# kbd.net
KiCad netlist of a schematic drawn in Altium Designer
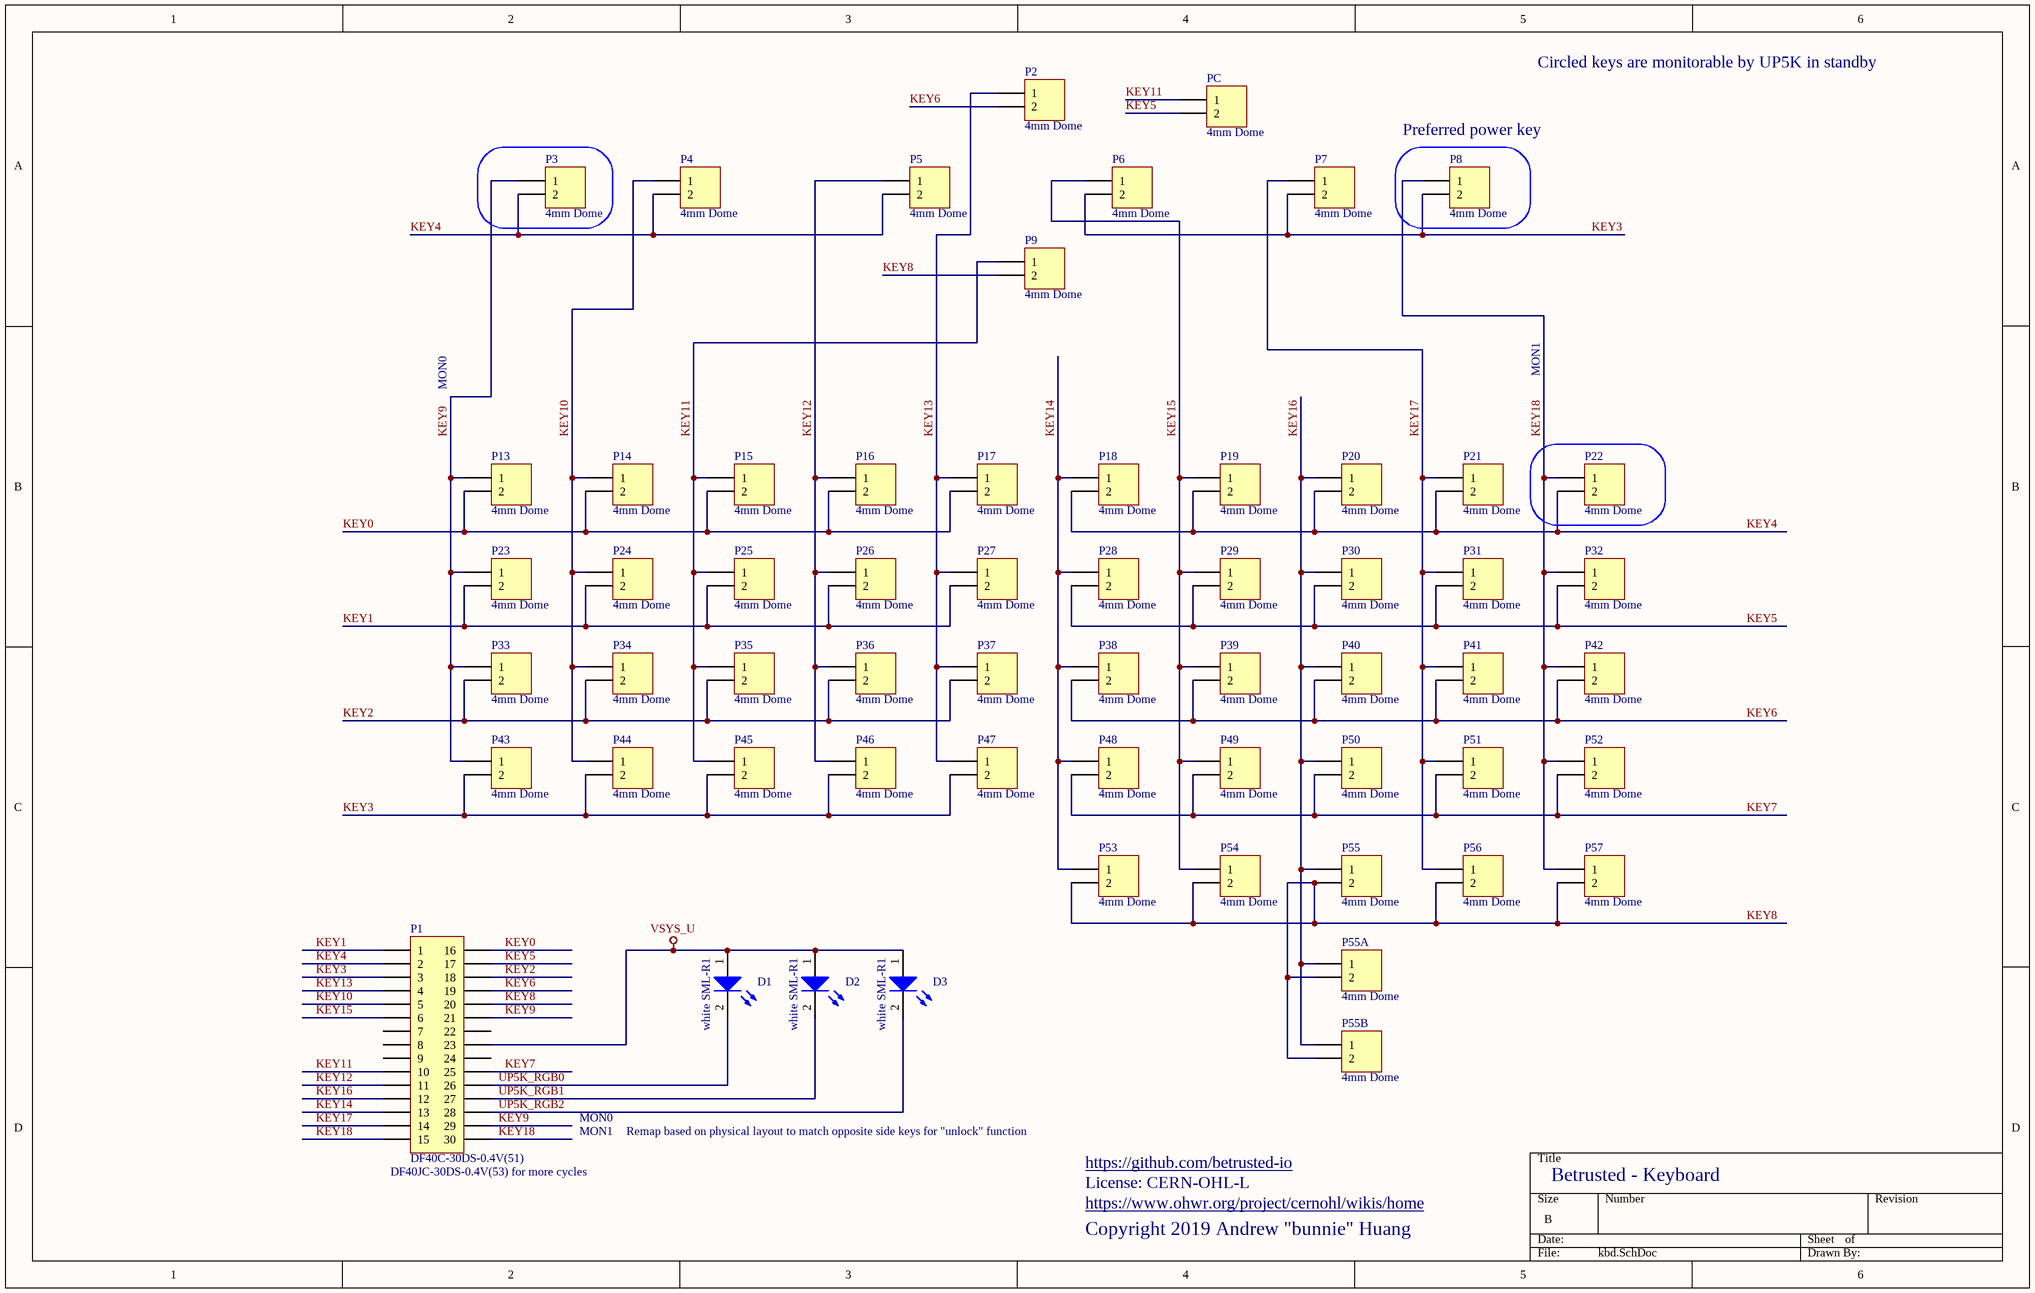
[diagram p0: kbd.SchDoc]

(export (version "E")
  (design (tool "Eeschema 10.0.6"))
  (components
    (comp (ref "D1")
      (value "white SML-R1")
      (footprint "ROHM_SML-R1")
      (description "Red LED")
      (fields (field (name "MPN") "SMLR13WBDW") (field (name "PUBLISHER") "Altium Limited"))
      (libsource (lib "Miscellaneous Devices") (part "LED2"))
    )
    (comp (ref "D2")
      (value "white SML-R1")
      (footprint "ROHM_SML-R1")
      (description "Red LED")
      (fields (field (name "MPN") "SMLR13WBDW") (field (name "PUBLISHER") "Altium Limited"))
      (libsource (lib "Miscellaneous Devices") (part "LED2"))
    )
    (comp (ref "D3")
      (value "white SML-R1")
      (footprint "ROHM_SML-R1")
      (description "Red LED")
      (fields (field (name "MPN") "SMLR13WBDW") (field (name "PUBLISHER") "Altium Limited"))
      (libsource (lib "Miscellaneous Devices") (part "LED2"))
    )
    (comp (ref "P1")
      (value "DF40C-30DS-0.4V(51)")
      (footprint "HRS_DF40C-30DS-0.4V(51)")
      (description "Header, 15-Pin, Dual row")
      (fields (field (name "PUBLISHER") "Altium Limited"))
      (libsource (lib "Miscellaneous Connectors") (part "Header 15X2A"))
    )
    (comp (ref "P2")
      (value "4mm Dome")
      (footprint "4MM_DOME_SW")
      (description "Header, 2-Pin")
      (fields (field (name "PUBLISHER") "Altium Limited"))
      (libsource (lib "Miscellaneous Connectors") (part "Header 2"))
    )
    (comp (ref "P3")
      (value "4mm Dome")
      (footprint "4MM_DOME_SW")
      (description "Header, 2-Pin")
      (fields (field (name "PUBLISHER") "Altium Limited"))
      (libsource (lib "Miscellaneous Connectors") (part "Header 2"))
    )
    (comp (ref "P4")
      (value "4mm Dome")
      (footprint "4MM_DOME_SW")
      (description "Header, 2-Pin")
      (fields (field (name "PUBLISHER") "Altium Limited"))
      (libsource (lib "Miscellaneous Connectors") (part "Header 2"))
    )
    (comp (ref "P5")
      (value "4mm Dome")
      (footprint "4MM_DOME_SW")
      (description "Header, 2-Pin")
      (fields (field (name "PUBLISHER") "Altium Limited"))
      (libsource (lib "Miscellaneous Connectors") (part "Header 2"))
    )
    (comp (ref "P6")
      (value "4mm Dome")
      (footprint "4MM_DOME_SW")
      (description "Header, 2-Pin")
      (fields (field (name "PUBLISHER") "Altium Limited"))
      (libsource (lib "Miscellaneous Connectors") (part "Header 2"))
    )
    (comp (ref "P7")
      (value "4mm Dome")
      (footprint "4MM_DOME_SW")
      (description "Header, 2-Pin")
      (fields (field (name "PUBLISHER") "Altium Limited"))
      (libsource (lib "Miscellaneous Connectors") (part "Header 2"))
    )
    (comp (ref "P8")
      (value "4mm Dome")
      (footprint "4MM_DOME_SW")
      (description "Header, 2-Pin")
      (fields (field (name "PUBLISHER") "Altium Limited"))
      (libsource (lib "Miscellaneous Connectors") (part "Header 2"))
    )
    (comp (ref "P9")
      (value "4mm Dome")
      (footprint "4MM_DOME_SW")
      (description "Header, 2-Pin")
      (fields (field (name "PUBLISHER") "Altium Limited"))
      (libsource (lib "Miscellaneous Connectors") (part "Header 2"))
    )
    (comp (ref "P13")
      (value "4mm Dome")
      (footprint "4MM_DOME_SW")
      (description "Header, 2-Pin")
      (fields (field (name "PUBLISHER") "Altium Limited"))
      (libsource (lib "Miscellaneous Connectors") (part "Header 2"))
    )
    (comp (ref "P14")
      (value "4mm Dome")
      (footprint "4MM_DOME_SW")
      (description "Header, 2-Pin")
      (fields (field (name "PUBLISHER") "Altium Limited"))
      (libsource (lib "Miscellaneous Connectors") (part "Header 2"))
    )
    (comp (ref "P15")
      (value "4mm Dome")
      (footprint "4MM_DOME_SW")
      (description "Header, 2-Pin")
      (fields (field (name "PUBLISHER") "Altium Limited"))
      (libsource (lib "Miscellaneous Connectors") (part "Header 2"))
    )
    (comp (ref "P16")
      (value "4mm Dome")
      (footprint "4MM_DOME_SW")
      (description "Header, 2-Pin")
      (fields (field (name "PUBLISHER") "Altium Limited"))
      (libsource (lib "Miscellaneous Connectors") (part "Header 2"))
    )
    (comp (ref "P17")
      (value "4mm Dome")
      (footprint "4MM_DOME_SW")
      (description "Header, 2-Pin")
      (fields (field (name "PUBLISHER") "Altium Limited"))
      (libsource (lib "Miscellaneous Connectors") (part "Header 2"))
    )
    (comp (ref "P18")
      (value "4mm Dome")
      (footprint "4MM_DOME_SW")
      (description "Header, 2-Pin")
      (fields (field (name "PUBLISHER") "Altium Limited"))
      (libsource (lib "Miscellaneous Connectors") (part "Header 2"))
    )
    (comp (ref "P19")
      (value "4mm Dome")
      (footprint "4MM_DOME_SW")
      (description "Header, 2-Pin")
      (fields (field (name "PUBLISHER") "Altium Limited"))
      (libsource (lib "Miscellaneous Connectors") (part "Header 2"))
    )
    (comp (ref "P20")
      (value "4mm Dome")
      (footprint "4MM_DOME_SW")
      (description "Header, 2-Pin")
      (fields (field (name "PUBLISHER") "Altium Limited"))
      (libsource (lib "Miscellaneous Connectors") (part "Header 2"))
    )
    (comp (ref "P21")
      (value "4mm Dome")
      (footprint "4MM_DOME_SW")
      (description "Header, 2-Pin")
      (fields (field (name "PUBLISHER") "Altium Limited"))
      (libsource (lib "Miscellaneous Connectors") (part "Header 2"))
    )
    (comp (ref "P22")
      (value "4mm Dome")
      (footprint "4MM_DOME_SW")
      (description "Header, 2-Pin")
      (fields (field (name "PUBLISHER") "Altium Limited"))
      (libsource (lib "Miscellaneous Connectors") (part "Header 2"))
    )
    (comp (ref "P23")
      (value "4mm Dome")
      (footprint "4MM_DOME_SW")
      (description "Header, 2-Pin")
      (fields (field (name "PUBLISHER") "Altium Limited"))
      (libsource (lib "Miscellaneous Connectors") (part "Header 2"))
    )
    (comp (ref "P24")
      (value "4mm Dome")
      (footprint "4MM_DOME_SW")
      (description "Header, 2-Pin")
      (fields (field (name "PUBLISHER") "Altium Limited"))
      (libsource (lib "Miscellaneous Connectors") (part "Header 2"))
    )
    (comp (ref "P25")
      (value "4mm Dome")
      (footprint "4MM_DOME_SW")
      (description "Header, 2-Pin")
      (fields (field (name "PUBLISHER") "Altium Limited"))
      (libsource (lib "Miscellaneous Connectors") (part "Header 2"))
    )
    (comp (ref "P26")
      (value "4mm Dome")
      (footprint "4MM_DOME_SW")
      (description "Header, 2-Pin")
      (fields (field (name "PUBLISHER") "Altium Limited"))
      (libsource (lib "Miscellaneous Connectors") (part "Header 2"))
    )
    (comp (ref "P27")
      (value "4mm Dome")
      (footprint "4MM_DOME_SW")
      (description "Header, 2-Pin")
      (fields (field (name "PUBLISHER") "Altium Limited"))
      (libsource (lib "Miscellaneous Connectors") (part "Header 2"))
    )
    (comp (ref "P28")
      (value "4mm Dome")
      (footprint "4MM_DOME_SW")
      (description "Header, 2-Pin")
      (fields (field (name "PUBLISHER") "Altium Limited"))
      (libsource (lib "Miscellaneous Connectors") (part "Header 2"))
    )
    (comp (ref "P29")
      (value "4mm Dome")
      (footprint "4MM_DOME_SW")
      (description "Header, 2-Pin")
      (fields (field (name "PUBLISHER") "Altium Limited"))
      (libsource (lib "Miscellaneous Connectors") (part "Header 2"))
    )
    (comp (ref "P30")
      (value "4mm Dome")
      (footprint "4MM_DOME_SW")
      (description "Header, 2-Pin")
      (fields (field (name "PUBLISHER") "Altium Limited"))
      (libsource (lib "Miscellaneous Connectors") (part "Header 2"))
    )
    (comp (ref "P31")
      (value "4mm Dome")
      (footprint "4MM_DOME_SW")
      (description "Header, 2-Pin")
      (fields (field (name "PUBLISHER") "Altium Limited"))
      (libsource (lib "Miscellaneous Connectors") (part "Header 2"))
    )
    (comp (ref "P32")
      (value "4mm Dome")
      (footprint "4MM_DOME_SW")
      (description "Header, 2-Pin")
      (fields (field (name "PUBLISHER") "Altium Limited"))
      (libsource (lib "Miscellaneous Connectors") (part "Header 2"))
    )
    (comp (ref "P33")
      (value "4mm Dome")
      (footprint "4MM_DOME_SW")
      (description "Header, 2-Pin")
      (fields (field (name "PUBLISHER") "Altium Limited"))
      (libsource (lib "Miscellaneous Connectors") (part "Header 2"))
    )
    (comp (ref "P34")
      (value "4mm Dome")
      (footprint "4MM_DOME_SW")
      (description "Header, 2-Pin")
      (fields (field (name "PUBLISHER") "Altium Limited"))
      (libsource (lib "Miscellaneous Connectors") (part "Header 2"))
    )
    (comp (ref "P35")
      (value "4mm Dome")
      (footprint "4MM_DOME_SW")
      (description "Header, 2-Pin")
      (fields (field (name "PUBLISHER") "Altium Limited"))
      (libsource (lib "Miscellaneous Connectors") (part "Header 2"))
    )
    (comp (ref "P36")
      (value "4mm Dome")
      (footprint "4MM_DOME_SW")
      (description "Header, 2-Pin")
      (fields (field (name "PUBLISHER") "Altium Limited"))
      (libsource (lib "Miscellaneous Connectors") (part "Header 2"))
    )
    (comp (ref "P37")
      (value "4mm Dome")
      (footprint "4MM_DOME_SW")
      (description "Header, 2-Pin")
      (fields (field (name "PUBLISHER") "Altium Limited"))
      (libsource (lib "Miscellaneous Connectors") (part "Header 2"))
    )
    (comp (ref "P38")
      (value "4mm Dome")
      (footprint "4MM_DOME_SW")
      (description "Header, 2-Pin")
      (fields (field (name "PUBLISHER") "Altium Limited"))
      (libsource (lib "Miscellaneous Connectors") (part "Header 2"))
    )
    (comp (ref "P39")
      (value "4mm Dome")
      (footprint "4MM_DOME_SW")
      (description "Header, 2-Pin")
      (fields (field (name "PUBLISHER") "Altium Limited"))
      (libsource (lib "Miscellaneous Connectors") (part "Header 2"))
    )
    (comp (ref "P40")
      (value "4mm Dome")
      (footprint "4MM_DOME_SW")
      (description "Header, 2-Pin")
      (fields (field (name "PUBLISHER") "Altium Limited"))
      (libsource (lib "Miscellaneous Connectors") (part "Header 2"))
    )
    (comp (ref "P41")
      (value "4mm Dome")
      (footprint "4MM_DOME_SW")
      (description "Header, 2-Pin")
      (fields (field (name "PUBLISHER") "Altium Limited"))
      (libsource (lib "Miscellaneous Connectors") (part "Header 2"))
    )
    (comp (ref "P42")
      (value "4mm Dome")
      (footprint "4MM_DOME_SW")
      (description "Header, 2-Pin")
      (fields (field (name "PUBLISHER") "Altium Limited"))
      (libsource (lib "Miscellaneous Connectors") (part "Header 2"))
    )
    (comp (ref "P43")
      (value "4mm Dome")
      (footprint "4MM_DOME_SW")
      (description "Header, 2-Pin")
      (fields (field (name "PUBLISHER") "Altium Limited"))
      (libsource (lib "Miscellaneous Connectors") (part "Header 2"))
    )
    (comp (ref "P44")
      (value "4mm Dome")
      (footprint "4MM_DOME_SW")
      (description "Header, 2-Pin")
      (fields (field (name "PUBLISHER") "Altium Limited"))
      (libsource (lib "Miscellaneous Connectors") (part "Header 2"))
    )
    (comp (ref "P45")
      (value "4mm Dome")
      (footprint "4MM_DOME_SW")
      (description "Header, 2-Pin")
      (fields (field (name "PUBLISHER") "Altium Limited"))
      (libsource (lib "Miscellaneous Connectors") (part "Header 2"))
    )
    (comp (ref "P46")
      (value "4mm Dome")
      (footprint "4MM_DOME_SW")
      (description "Header, 2-Pin")
      (fields (field (name "PUBLISHER") "Altium Limited"))
      (libsource (lib "Miscellaneous Connectors") (part "Header 2"))
    )
    (comp (ref "P47")
      (value "4mm Dome")
      (footprint "4MM_DOME_SW")
      (description "Header, 2-Pin")
      (fields (field (name "PUBLISHER") "Altium Limited"))
      (libsource (lib "Miscellaneous Connectors") (part "Header 2"))
    )
    (comp (ref "P48")
      (value "4mm Dome")
      (footprint "4MM_DOME_SW")
      (description "Header, 2-Pin")
      (fields (field (name "PUBLISHER") "Altium Limited"))
      (libsource (lib "Miscellaneous Connectors") (part "Header 2"))
    )
    (comp (ref "P49")
      (value "4mm Dome")
      (footprint "4MM_DOME_SW")
      (description "Header, 2-Pin")
      (fields (field (name "PUBLISHER") "Altium Limited"))
      (libsource (lib "Miscellaneous Connectors") (part "Header 2"))
    )
    (comp (ref "P50")
      (value "4mm Dome")
      (footprint "4MM_DOME_SW")
      (description "Header, 2-Pin")
      (fields (field (name "PUBLISHER") "Altium Limited"))
      (libsource (lib "Miscellaneous Connectors") (part "Header 2"))
    )
    (comp (ref "P51")
      (value "4mm Dome")
      (footprint "4MM_DOME_SW")
      (description "Header, 2-Pin")
      (fields (field (name "PUBLISHER") "Altium Limited"))
      (libsource (lib "Miscellaneous Connectors") (part "Header 2"))
    )
    (comp (ref "P52")
      (value "4mm Dome")
      (footprint "4MM_DOME_SW")
      (description "Header, 2-Pin")
      (fields (field (name "PUBLISHER") "Altium Limited"))
      (libsource (lib "Miscellaneous Connectors") (part "Header 2"))
    )
    (comp (ref "P53")
      (value "4mm Dome")
      (footprint "4MM_DOME_SW")
      (description "Header, 2-Pin")
      (fields (field (name "PUBLISHER") "Altium Limited"))
      (libsource (lib "Miscellaneous Connectors") (part "Header 2"))
    )
    (comp (ref "P54")
      (value "4mm Dome")
      (footprint "4MM_DOME_SW")
      (description "Header, 2-Pin")
      (fields (field (name "PUBLISHER") "Altium Limited"))
      (libsource (lib "Miscellaneous Connectors") (part "Header 2"))
    )
    (comp (ref "P55")
      (value "4mm Dome")
      (footprint "4MM_DOME_SW")
      (description "Header, 2-Pin")
      (fields (field (name "PUBLISHER") "Altium Limited"))
      (libsource (lib "Miscellaneous Connectors") (part "Header 2"))
    )
    (comp (ref "P55A")
      (value "4mm Dome")
      (footprint "4MM_DOME_SW")
      (description "Header, 2-Pin")
      (fields (field (name "PUBLISHER") "Altium Limited"))
      (libsource (lib "Miscellaneous Connectors") (part "Header 2"))
    )
    (comp (ref "P55B")
      (value "4mm Dome")
      (footprint "4MM_DOME_SW")
      (description "Header, 2-Pin")
      (fields (field (name "PUBLISHER") "Altium Limited"))
      (libsource (lib "Miscellaneous Connectors") (part "Header 2"))
    )
    (comp (ref "P56")
      (value "4mm Dome")
      (footprint "4MM_DOME_SW")
      (description "Header, 2-Pin")
      (fields (field (name "PUBLISHER") "Altium Limited"))
      (libsource (lib "Miscellaneous Connectors") (part "Header 2"))
    )
    (comp (ref "P57")
      (value "4mm Dome")
      (footprint "4MM_DOME_SW")
      (description "Header, 2-Pin")
      (fields (field (name "PUBLISHER") "Altium Limited"))
      (libsource (lib "Miscellaneous Connectors") (part "Header 2"))
    )
    (comp (ref "PC")
      (value "4mm Dome")
      (footprint "4MM_DOME_SW")
      (description "Header, 2-Pin")
      (fields (field (name "PUBLISHER") "Altium Limited"))
      (libsource (lib "Miscellaneous Connectors") (part "Header 2"))
    )
  )
  (nets
    (net (code "1") (name "/KEY0") (class "Default")
      (node (ref "P1") (pin "16") (pinfunction "16_16") (pintype "passive"))
      (node (ref "P13") (pin "2") (pinfunction "2_2") (pintype "passive"))
      (node (ref "P14") (pin "2") (pinfunction "2_2") (pintype "passive"))
      (node (ref "P15") (pin "2") (pinfunction "2_2") (pintype "passive"))
      (node (ref "P16") (pin "2") (pinfunction "2_2") (pintype "passive"))
      (node (ref "P17") (pin "2") (pinfunction "2_2") (pintype "passive"))
    )
    (net (code "2") (name "/KEY1") (class "Default")
      (node (ref "P1") (pin "1") (pinfunction "1_1") (pintype "passive"))
      (node (ref "P23") (pin "2") (pinfunction "2_2") (pintype "passive"))
      (node (ref "P24") (pin "2") (pinfunction "2_2") (pintype "passive"))
      (node (ref "P25") (pin "2") (pinfunction "2_2") (pintype "passive"))
      (node (ref "P26") (pin "2") (pinfunction "2_2") (pintype "passive"))
      (node (ref "P27") (pin "2") (pinfunction "2_2") (pintype "passive"))
    )
    (net (code "3") (name "/KEY2") (class "Default")
      (node (ref "P1") (pin "18") (pinfunction "18_18") (pintype "passive"))
      (node (ref "P33") (pin "2") (pinfunction "2_2") (pintype "passive"))
      (node (ref "P34") (pin "2") (pinfunction "2_2") (pintype "passive"))
      (node (ref "P35") (pin "2") (pinfunction "2_2") (pintype "passive"))
      (node (ref "P36") (pin "2") (pinfunction "2_2") (pintype "passive"))
      (node (ref "P37") (pin "2") (pinfunction "2_2") (pintype "passive"))
    )
    (net (code "4") (name "/KEY3") (class "Default")
      (node (ref "P1") (pin "3") (pinfunction "3_3") (pintype "passive"))
      (node (ref "P43") (pin "2") (pinfunction "2_2") (pintype "passive"))
      (node (ref "P44") (pin "2") (pinfunction "2_2") (pintype "passive"))
      (node (ref "P45") (pin "2") (pinfunction "2_2") (pintype "passive"))
      (node (ref "P46") (pin "2") (pinfunction "2_2") (pintype "passive"))
      (node (ref "P47") (pin "2") (pinfunction "2_2") (pintype "passive"))
      (node (ref "P6") (pin "2") (pinfunction "2_2") (pintype "passive"))
      (node (ref "P7") (pin "2") (pinfunction "2_2") (pintype "passive"))
      (node (ref "P8") (pin "2") (pinfunction "2_2") (pintype "passive"))
    )
    (net (code "5") (name "/KEY4") (class "Default")
      (node (ref "P1") (pin "2") (pinfunction "2_2") (pintype "passive"))
      (node (ref "P18") (pin "2") (pinfunction "2_2") (pintype "passive"))
      (node (ref "P19") (pin "2") (pinfunction "2_2") (pintype "passive"))
      (node (ref "P20") (pin "2") (pinfunction "2_2") (pintype "passive"))
      (node (ref "P21") (pin "2") (pinfunction "2_2") (pintype "passive"))
      (node (ref "P22") (pin "2") (pinfunction "2_2") (pintype "passive"))
      (node (ref "P3") (pin "2") (pinfunction "2_2") (pintype "passive"))
      (node (ref "P4") (pin "2") (pinfunction "2_2") (pintype "passive"))
      (node (ref "P5") (pin "2") (pinfunction "2_2") (pintype "passive"))
    )
    (net (code "6") (name "/KEY5") (class "Default")
      (node (ref "P1") (pin "17") (pinfunction "17_17") (pintype "passive"))
      (node (ref "P28") (pin "2") (pinfunction "2_2") (pintype "passive"))
      (node (ref "P29") (pin "2") (pinfunction "2_2") (pintype "passive"))
      (node (ref "P30") (pin "2") (pinfunction "2_2") (pintype "passive"))
      (node (ref "P31") (pin "2") (pinfunction "2_2") (pintype "passive"))
      (node (ref "P32") (pin "2") (pinfunction "2_2") (pintype "passive"))
      (node (ref "PC") (pin "2") (pinfunction "2_2") (pintype "passive"))
    )
    (net (code "7") (name "/KEY6") (class "Default")
      (node (ref "P1") (pin "19") (pinfunction "19_19") (pintype "passive"))
      (node (ref "P2") (pin "2") (pinfunction "2_2") (pintype "passive"))
      (node (ref "P38") (pin "2") (pinfunction "2_2") (pintype "passive"))
      (node (ref "P39") (pin "2") (pinfunction "2_2") (pintype "passive"))
      (node (ref "P40") (pin "2") (pinfunction "2_2") (pintype "passive"))
      (node (ref "P41") (pin "2") (pinfunction "2_2") (pintype "passive"))
      (node (ref "P42") (pin "2") (pinfunction "2_2") (pintype "passive"))
    )
    (net (code "8") (name "/KEY7") (class "Default")
      (node (ref "P1") (pin "25") (pinfunction "25_25") (pintype "passive"))
      (node (ref "P48") (pin "2") (pinfunction "2_2") (pintype "passive"))
      (node (ref "P49") (pin "2") (pinfunction "2_2") (pintype "passive"))
      (node (ref "P50") (pin "2") (pinfunction "2_2") (pintype "passive"))
      (node (ref "P51") (pin "2") (pinfunction "2_2") (pintype "passive"))
      (node (ref "P52") (pin "2") (pinfunction "2_2") (pintype "passive"))
    )
    (net (code "9") (name "/KEY8") (class "Default")
      (node (ref "P1") (pin "20") (pinfunction "20_20") (pintype "passive"))
      (node (ref "P53") (pin "2") (pinfunction "2_2") (pintype "passive"))
      (node (ref "P54") (pin "2") (pinfunction "2_2") (pintype "passive"))
      (node (ref "P55") (pin "2") (pinfunction "2_2") (pintype "passive"))
      (node (ref "P55A") (pin "2") (pinfunction "2_2") (pintype "passive"))
      (node (ref "P55B") (pin "2") (pinfunction "2_2") (pintype "passive"))
      (node (ref "P56") (pin "2") (pinfunction "2_2") (pintype "passive"))
      (node (ref "P57") (pin "2") (pinfunction "2_2") (pintype "passive"))
      (node (ref "P9") (pin "2") (pinfunction "2_2") (pintype "passive"))
    )
    (net (code "10") (name "/KEY9") (class "Default")
      (node (ref "P1") (pin "21") (pinfunction "21_21") (pintype "passive"))
      (node (ref "P1") (pin "29") (pinfunction "29_29") (pintype "passive"))
      (node (ref "P13") (pin "1") (pinfunction "1_1") (pintype "passive"))
      (node (ref "P23") (pin "1") (pinfunction "1_1") (pintype "passive"))
      (node (ref "P3") (pin "1") (pinfunction "1_1") (pintype "passive"))
      (node (ref "P33") (pin "1") (pinfunction "1_1") (pintype "passive"))
      (node (ref "P43") (pin "1") (pinfunction "1_1") (pintype "passive"))
    )
    (net (code "11") (name "/KEY10") (class "Default")
      (node (ref "P1") (pin "5") (pinfunction "5_5") (pintype "passive"))
      (node (ref "P14") (pin "1") (pinfunction "1_1") (pintype "passive"))
      (node (ref "P24") (pin "1") (pinfunction "1_1") (pintype "passive"))
      (node (ref "P34") (pin "1") (pinfunction "1_1") (pintype "passive"))
      (node (ref "P4") (pin "1") (pinfunction "1_1") (pintype "passive"))
      (node (ref "P44") (pin "1") (pinfunction "1_1") (pintype "passive"))
    )
    (net (code "12") (name "/KEY11") (class "Default")
      (node (ref "P1") (pin "10") (pinfunction "10_10") (pintype "passive"))
      (node (ref "P15") (pin "1") (pinfunction "1_1") (pintype "passive"))
      (node (ref "P25") (pin "1") (pinfunction "1_1") (pintype "passive"))
      (node (ref "P35") (pin "1") (pinfunction "1_1") (pintype "passive"))
      (node (ref "P45") (pin "1") (pinfunction "1_1") (pintype "passive"))
      (node (ref "P9") (pin "1") (pinfunction "1_1") (pintype "passive"))
      (node (ref "PC") (pin "1") (pinfunction "1_1") (pintype "passive"))
    )
    (net (code "13") (name "/KEY12") (class "Default")
      (node (ref "P1") (pin "11") (pinfunction "11_11") (pintype "passive"))
      (node (ref "P16") (pin "1") (pinfunction "1_1") (pintype "passive"))
      (node (ref "P26") (pin "1") (pinfunction "1_1") (pintype "passive"))
      (node (ref "P36") (pin "1") (pinfunction "1_1") (pintype "passive"))
      (node (ref "P46") (pin "1") (pinfunction "1_1") (pintype "passive"))
      (node (ref "P5") (pin "1") (pinfunction "1_1") (pintype "passive"))
    )
    (net (code "14") (name "/KEY13") (class "Default")
      (node (ref "P1") (pin "4") (pinfunction "4_4") (pintype "passive"))
      (node (ref "P17") (pin "1") (pinfunction "1_1") (pintype "passive"))
      (node (ref "P2") (pin "1") (pinfunction "1_1") (pintype "passive"))
      (node (ref "P27") (pin "1") (pinfunction "1_1") (pintype "passive"))
      (node (ref "P37") (pin "1") (pinfunction "1_1") (pintype "passive"))
      (node (ref "P47") (pin "1") (pinfunction "1_1") (pintype "passive"))
    )
    (net (code "15") (name "/KEY14") (class "Default")
      (node (ref "P1") (pin "13") (pinfunction "13_13") (pintype "passive"))
      (node (ref "P18") (pin "1") (pinfunction "1_1") (pintype "passive"))
      (node (ref "P28") (pin "1") (pinfunction "1_1") (pintype "passive"))
      (node (ref "P38") (pin "1") (pinfunction "1_1") (pintype "passive"))
      (node (ref "P48") (pin "1") (pinfunction "1_1") (pintype "passive"))
      (node (ref "P53") (pin "1") (pinfunction "1_1") (pintype "passive"))
    )
    (net (code "16") (name "/KEY15") (class "Default")
      (node (ref "P1") (pin "6") (pinfunction "6_6") (pintype "passive"))
      (node (ref "P19") (pin "1") (pinfunction "1_1") (pintype "passive"))
      (node (ref "P29") (pin "1") (pinfunction "1_1") (pintype "passive"))
      (node (ref "P39") (pin "1") (pinfunction "1_1") (pintype "passive"))
      (node (ref "P49") (pin "1") (pinfunction "1_1") (pintype "passive"))
      (node (ref "P54") (pin "1") (pinfunction "1_1") (pintype "passive"))
      (node (ref "P6") (pin "1") (pinfunction "1_1") (pintype "passive"))
    )
    (net (code "17") (name "/KEY16") (class "Default")
      (node (ref "P1") (pin "12") (pinfunction "12_12") (pintype "passive"))
      (node (ref "P20") (pin "1") (pinfunction "1_1") (pintype "passive"))
      (node (ref "P30") (pin "1") (pinfunction "1_1") (pintype "passive"))
      (node (ref "P40") (pin "1") (pinfunction "1_1") (pintype "passive"))
      (node (ref "P50") (pin "1") (pinfunction "1_1") (pintype "passive"))
      (node (ref "P55") (pin "1") (pinfunction "1_1") (pintype "passive"))
      (node (ref "P55A") (pin "1") (pinfunction "1_1") (pintype "passive"))
      (node (ref "P55B") (pin "1") (pinfunction "1_1") (pintype "passive"))
    )
    (net (code "18") (name "/KEY17") (class "Default")
      (node (ref "P1") (pin "14") (pinfunction "14_14") (pintype "passive"))
      (node (ref "P21") (pin "1") (pinfunction "1_1") (pintype "passive"))
      (node (ref "P31") (pin "1") (pinfunction "1_1") (pintype "passive"))
      (node (ref "P41") (pin "1") (pinfunction "1_1") (pintype "passive"))
      (node (ref "P51") (pin "1") (pinfunction "1_1") (pintype "passive"))
      (node (ref "P56") (pin "1") (pinfunction "1_1") (pintype "passive"))
      (node (ref "P7") (pin "1") (pinfunction "1_1") (pintype "passive"))
    )
    (net (code "19") (name "/KEY18") (class "Default")
      (node (ref "P1") (pin "15") (pinfunction "15_15") (pintype "passive"))
      (node (ref "P1") (pin "30") (pinfunction "30_30") (pintype "passive"))
      (node (ref "P22") (pin "1") (pinfunction "1_1") (pintype "passive"))
      (node (ref "P32") (pin "1") (pinfunction "1_1") (pintype "passive"))
      (node (ref "P42") (pin "1") (pinfunction "1_1") (pintype "passive"))
      (node (ref "P52") (pin "1") (pinfunction "1_1") (pintype "passive"))
      (node (ref "P57") (pin "1") (pinfunction "1_1") (pintype "passive"))
      (node (ref "P8") (pin "1") (pinfunction "1_1") (pintype "passive"))
    )
    (net (code "20") (name "/UP5K_RGB0") (class "Default")
      (node (ref "D1") (pin "2") (pinfunction "K_2") (pintype "passive"))
      (node (ref "P1") (pin "26") (pinfunction "26_26") (pintype "passive"))
    )
    (net (code "21") (name "/UP5K_RGB1") (class "Default")
      (node (ref "D2") (pin "2") (pinfunction "K_2") (pintype "passive"))
      (node (ref "P1") (pin "27") (pinfunction "27_27") (pintype "passive"))
    )
    (net (code "22") (name "/UP5K_RGB2") (class "Default")
      (node (ref "D3") (pin "2") (pinfunction "K_2") (pintype "passive"))
      (node (ref "P1") (pin "28") (pinfunction "28_28") (pintype "passive"))
    )
    (net (code "23") (name "VSYS_U") (class "Default")
      (node (ref "D1") (pin "1") (pinfunction "A_1") (pintype "passive"))
      (node (ref "D2") (pin "1") (pinfunction "A_1") (pintype "passive"))
      (node (ref "D3") (pin "1") (pinfunction "A_1") (pintype "passive"))
      (node (ref "P1") (pin "23") (pinfunction "23_23") (pintype "passive"))
    )
    (net (code "24") (name "unconnected-(P1-Pad7)") (class "Default")
      (node (ref "P1") (pin "7") (pinfunction "7_7") (pintype "passive"))
    )
    (net (code "25") (name "unconnected-(P1-Pad8)") (class "Default")
      (node (ref "P1") (pin "8") (pinfunction "8_8") (pintype "passive"))
    )
    (net (code "26") (name "unconnected-(P1-Pad9)") (class "Default")
      (node (ref "P1") (pin "9") (pinfunction "9_9") (pintype "passive"))
    )
    (net (code "27") (name "unconnected-(P1-Pad22)") (class "Default")
      (node (ref "P1") (pin "22") (pinfunction "22_22") (pintype "passive"))
    )
    (net (code "28") (name "unconnected-(P1-Pad24)") (class "Default")
      (node (ref "P1") (pin "24") (pinfunction "24_24") (pintype "passive"))
    )
  )
)
